# demo_74HC595_Shift_register.net
KiCad netlist of a schematic drawn in EasyEDA
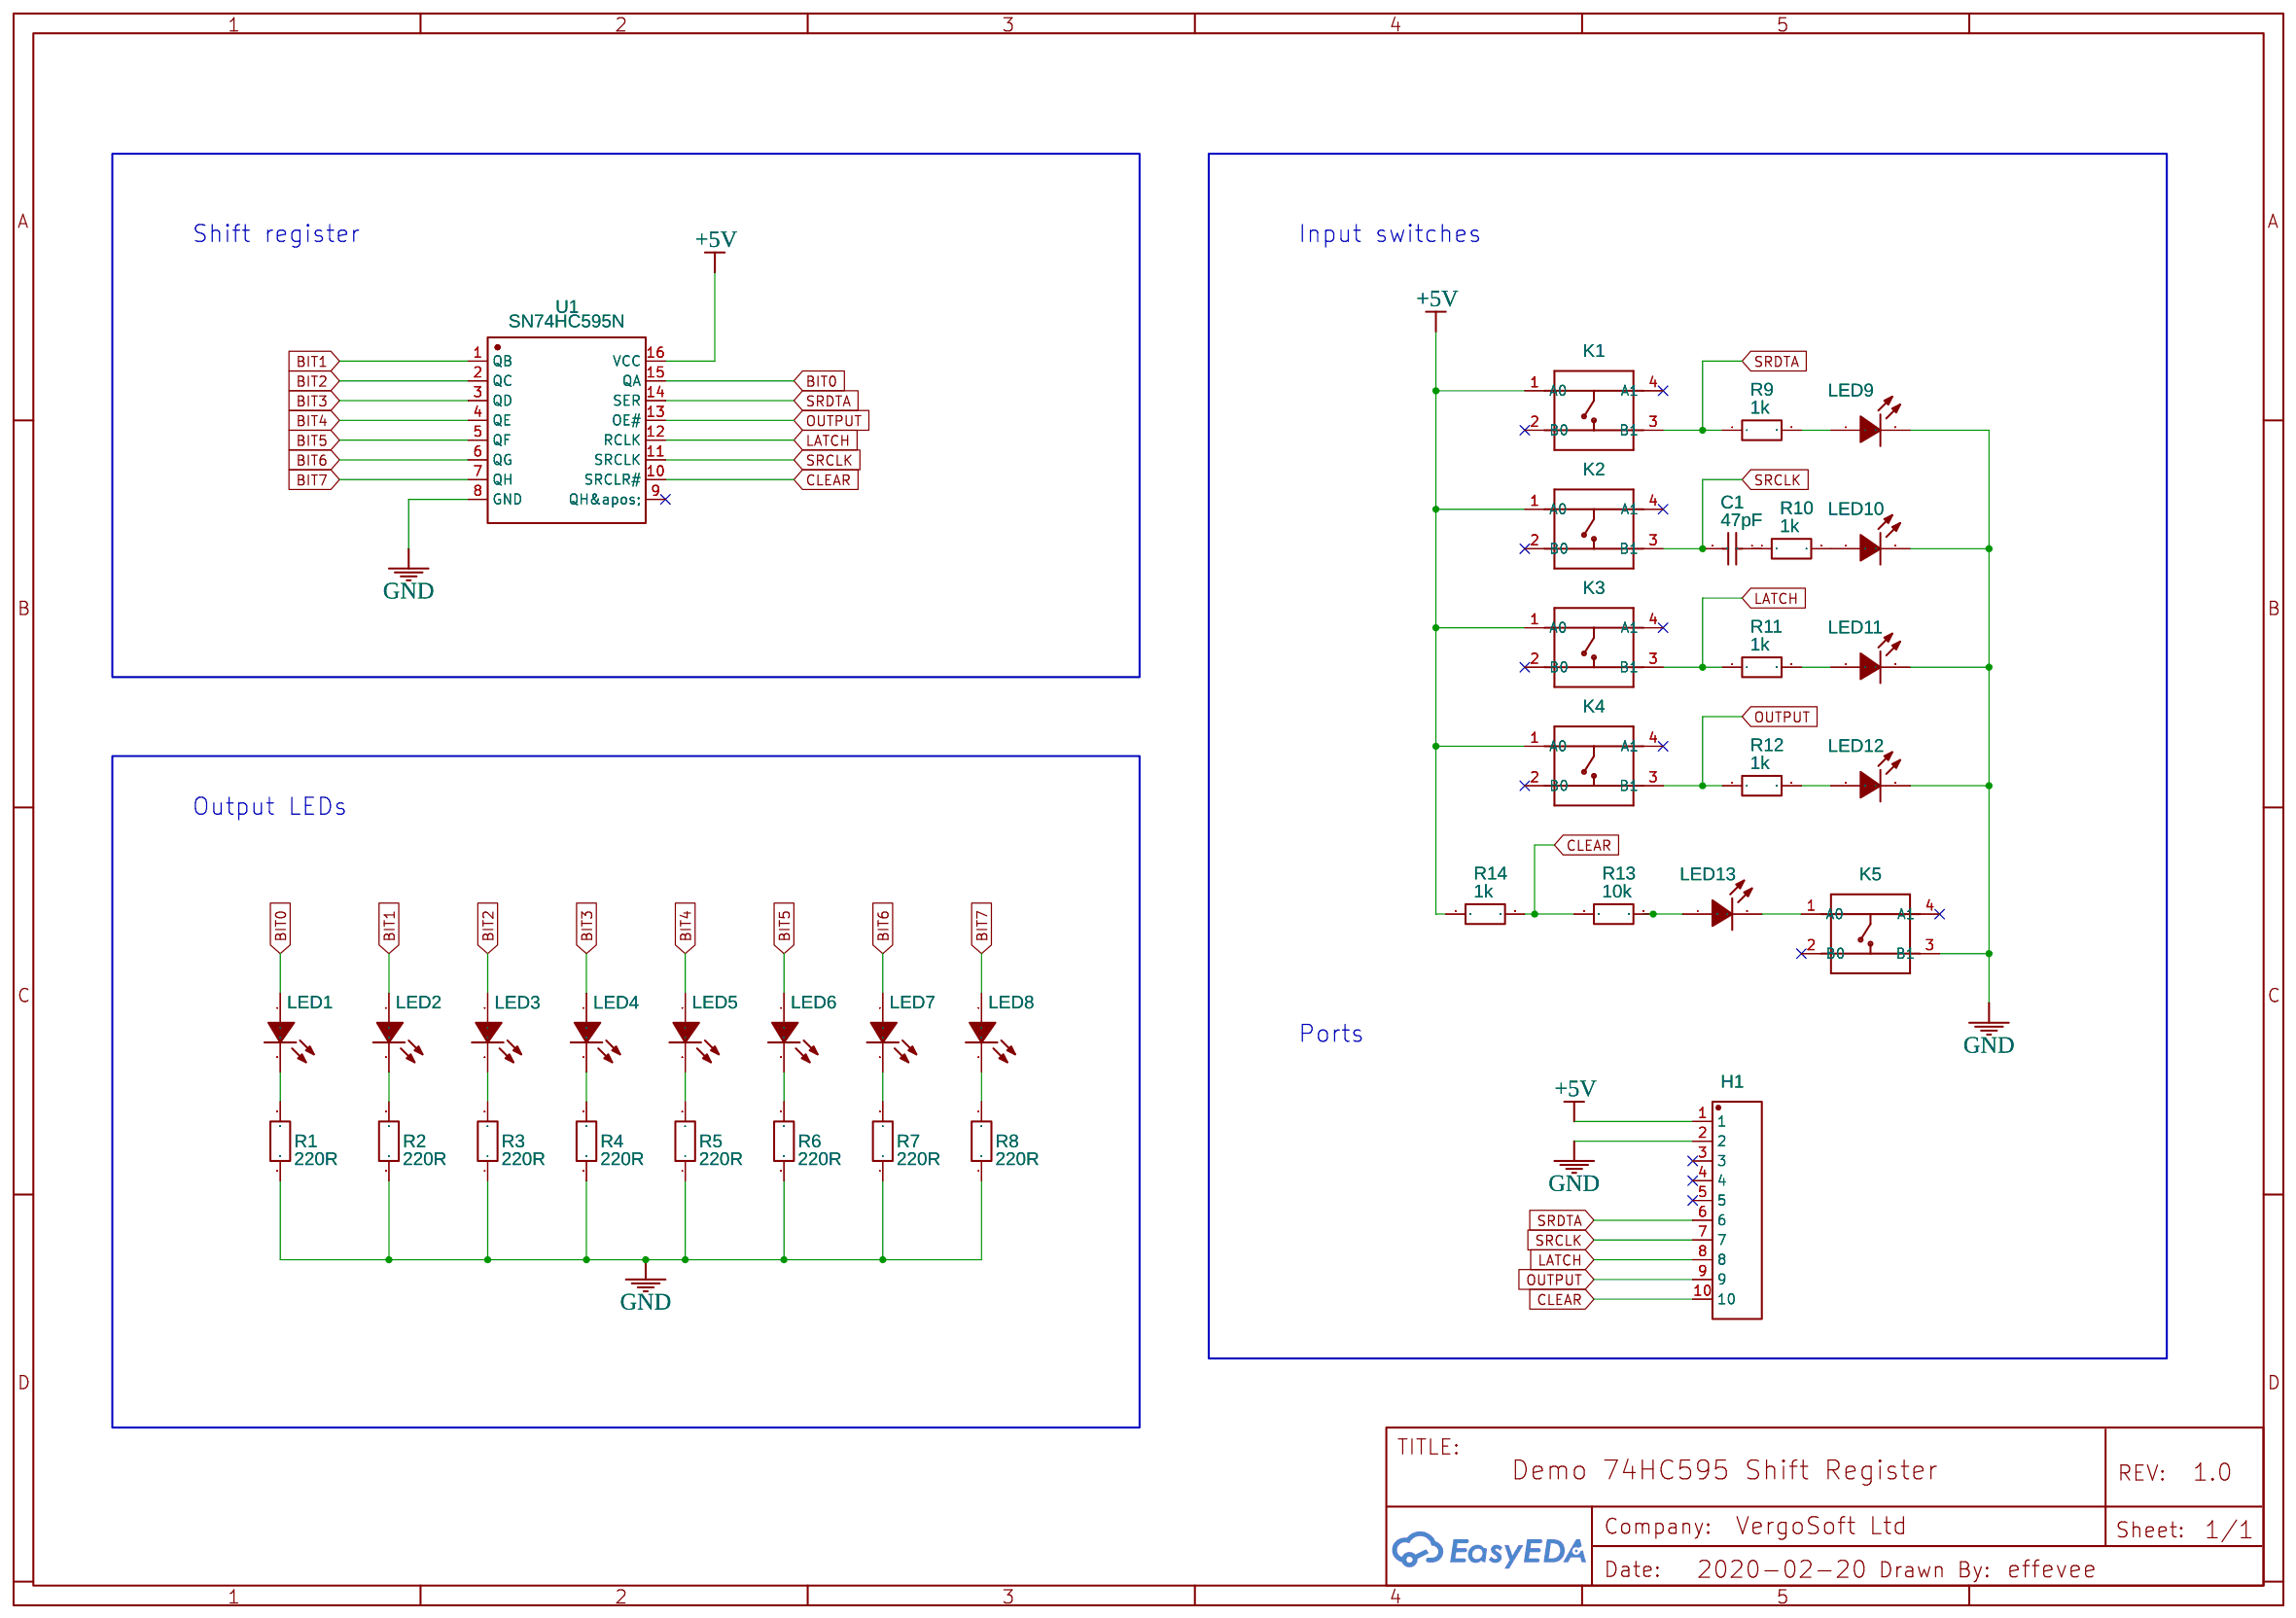
[diagram p0: schematic sheet]

(export (version "E")
  (design (tool "Eeschema 10.0.6"))
  (components
    (comp (ref "C1")
      (value "47pF")
      (fields
        (field (name "BOM_Manufacturer Part") "22pf/50V 10%")
        (field (name "BOM_Supplier Part") "C9316")
      )
      (libsource (lib "") (part "22pF"))
    )
    (comp (ref "H1")
      (value "Header-Male-2.54_1x10")
      (fields
        (field (name "BOM_Manufacturer Part") "Headers  Pins2.54mm1*10P")
        (field (name "BOM_Supplier Part") "C57369")
      )
      (libsource (lib "") (part "Header-Male-2.54_1x10"))
    )
    (comp (ref "K1")
      (value "DIP-SWITCH-TACTILE-SPST-NO_TS-1109(4P-D6.0MM)TS-1109")
      (libsource (lib "") (part "DIP-SWITCH-TACTILE-SPST-NO_TS-1109(4P-D6.0MM)TS-1109"))
    )
    (comp (ref "K2")
      (value "DIP-SWITCH-TACTILE-SPST-NO_TS-1109(4P-D6.0MM)TS-1109")
      (libsource (lib "") (part "DIP-SWITCH-TACTILE-SPST-NO_TS-1109(4P-D6.0MM)TS-1109"))
    )
    (comp (ref "K3")
      (value "DIP-SWITCH-TACTILE-SPST-NO_TS-1109(4P-D6.0MM)TS-1109")
      (libsource (lib "") (part "DIP-SWITCH-TACTILE-SPST-NO_TS-1109(4P-D6.0MM)TS-1109"))
    )
    (comp (ref "K4")
      (value "DIP-SWITCH-TACTILE-SPST-NO_TS-1109(4P-D6.0MM)TS-1109")
      (libsource (lib "") (part "DIP-SWITCH-TACTILE-SPST-NO_TS-1109(4P-D6.0MM)TS-1109"))
    )
    (comp (ref "K5")
      (value "DIP-SWITCH-TACTILE-SPST-NO_TS-1109(4P-D6.0MM)TS-1109")
      (libsource (lib "") (part "DIP-SWITCH-TACTILE-SPST-NO_TS-1109(4P-D6.0MM)TS-1109"))
    )
    (comp (ref "LED1")
      (value "204-10SURD/S530-A3")
      (fields (field (name "BOM_Supplier Part") "C99772"))
      (libsource (lib "") (part "204-10SURD/S530-A3"))
    )
    (comp (ref "LED2")
      (value "204-10SURD/S530-A3")
      (fields (field (name "BOM_Supplier Part") "C99772"))
      (libsource (lib "") (part "204-10SURD/S530-A3"))
    )
    (comp (ref "LED3")
      (value "204-10SURD/S530-A3")
      (fields (field (name "BOM_Supplier Part") "C99772"))
      (libsource (lib "") (part "204-10SURD/S530-A3"))
    )
    (comp (ref "LED4")
      (value "204-10SURD/S530-A3")
      (fields (field (name "BOM_Supplier Part") "C99772"))
      (libsource (lib "") (part "204-10SURD/S530-A3"))
    )
    (comp (ref "LED5")
      (value "204-10SURD/S530-A3")
      (fields (field (name "BOM_Supplier Part") "C99772"))
      (libsource (lib "") (part "204-10SURD/S530-A3"))
    )
    (comp (ref "LED6")
      (value "204-10SURD/S530-A3")
      (fields (field (name "BOM_Supplier Part") "C99772"))
      (libsource (lib "") (part "204-10SURD/S530-A3"))
    )
    (comp (ref "LED7")
      (value "204-10SURD/S530-A3")
      (fields (field (name "BOM_Supplier Part") "C99772"))
      (libsource (lib "") (part "204-10SURD/S530-A3"))
    )
    (comp (ref "LED8")
      (value "204-10SURD/S530-A3")
      (fields (field (name "BOM_Supplier Part") "C99772"))
      (libsource (lib "") (part "204-10SURD/S530-A3"))
    )
    (comp (ref "LED9")
      (value "204-10SURD/S530-A3")
      (fields (field (name "BOM_Supplier Part") "C99772"))
      (libsource (lib "") (part "204-10SURD/S530-A3_1"))
    )
    (comp (ref "LED10")
      (value "204-10SURD/S530-A3")
      (fields (field (name "BOM_Supplier Part") "C99772"))
      (libsource (lib "") (part "204-10SURD/S530-A3_1"))
    )
    (comp (ref "LED11")
      (value "204-10SURD/S530-A3")
      (fields (field (name "BOM_Supplier Part") "C99772"))
      (libsource (lib "") (part "204-10SURD/S530-A3_1"))
    )
    (comp (ref "LED12")
      (value "204-10SURD/S530-A3")
      (fields (field (name "BOM_Supplier Part") "C99772"))
      (libsource (lib "") (part "204-10SURD/S530-A3_1"))
    )
    (comp (ref "LED13")
      (value "204-10SURD/S530-A3")
      (fields (field (name "BOM_Supplier Part") "C99772"))
      (libsource (lib "") (part "204-10SURD/S530-A3_1"))
    )
    (comp (ref "R1") (value "220R") (libsource (lib "") (part "Res_AXIAL-0.3(1/8W)_EU")))
    (comp (ref "R2") (value "220R") (libsource (lib "") (part "Res_AXIAL-0.3(1/8W)_EU")))
    (comp (ref "R3") (value "220R") (libsource (lib "") (part "Res_AXIAL-0.3(1/8W)_EU")))
    (comp (ref "R4") (value "220R") (libsource (lib "") (part "Res_AXIAL-0.3(1/8W)_EU")))
    (comp (ref "R5") (value "220R") (libsource (lib "") (part "Res_AXIAL-0.3(1/8W)_EU")))
    (comp (ref "R6") (value "220R") (libsource (lib "") (part "Res_AXIAL-0.3(1/8W)_EU")))
    (comp (ref "R7") (value "220R") (libsource (lib "") (part "Res_AXIAL-0.3(1/8W)_EU")))
    (comp (ref "R8") (value "220R") (libsource (lib "") (part "Res_AXIAL-0.3(1/8W)_EU")))
    (comp (ref "R9") (value "1k") (libsource (lib "") (part "Res_AXIAL-0.3(1/8W)_EU_1")))
    (comp (ref "R10") (value "1k") (libsource (lib "") (part "Res_AXIAL-0.3(1/8W)_EU_1")))
    (comp (ref "R11") (value "1k") (libsource (lib "") (part "Res_AXIAL-0.3(1/8W)_EU_1")))
    (comp (ref "R12") (value "1k") (libsource (lib "") (part "Res_AXIAL-0.3(1/8W)_EU_1")))
    (comp (ref "R13") (value "10k") (libsource (lib "") (part "Res_AXIAL-0.3(1/8W)_EU_1")))
    (comp (ref "R14") (value "1k") (libsource (lib "") (part "Res_AXIAL-0.3(1/8W)_EU_1")))
    (comp (ref "U1")
      (value "SN74HC595N")
      (fields (field (name "BOM_Supplier Part") "C78711"))
      (libsource (lib "") (part "SN74HC595N"))
    )
  )
  (nets
    (net (code "1") (name "+5V") (class "Default")
      (node (ref "H1") (pin "1") (pinfunction "1_1") (pintype "unspecified"))
      (node (ref "K1") (pin "1") (pinfunction "A0_1") (pintype "unspecified"))
      (node (ref "K2") (pin "1") (pinfunction "A0_1") (pintype "unspecified"))
      (node (ref "K3") (pin "1") (pinfunction "A0_1") (pintype "unspecified"))
      (node (ref "K4") (pin "1") (pinfunction "A0_1") (pintype "unspecified"))
      (node (ref "R14") (pin "1") (pinfunction "1_1") (pintype "unspecified"))
      (node (ref "U1") (pin "16") (pinfunction "VCC_16") (pintype "unspecified"))
    )
    (net (code "2") (name "BIT0") (class "Default")
      (node (ref "LED1") (pin "1") (pinfunction "A_1") (pintype "unspecified"))
      (node (ref "U1") (pin "15") (pinfunction "QA_15") (pintype "unspecified"))
    )
    (net (code "3") (name "BIT1") (class "Default")
      (node (ref "LED2") (pin "1") (pinfunction "A_1") (pintype "unspecified"))
      (node (ref "U1") (pin "1") (pinfunction "QB_1") (pintype "unspecified"))
    )
    (net (code "4") (name "BIT2") (class "Default")
      (node (ref "LED3") (pin "1") (pinfunction "A_1") (pintype "unspecified"))
      (node (ref "U1") (pin "2") (pinfunction "QC_2") (pintype "unspecified"))
    )
    (net (code "5") (name "BIT3") (class "Default")
      (node (ref "LED4") (pin "1") (pinfunction "A_1") (pintype "unspecified"))
      (node (ref "U1") (pin "3") (pinfunction "QD_3") (pintype "unspecified"))
    )
    (net (code "6") (name "BIT4") (class "Default")
      (node (ref "LED5") (pin "1") (pinfunction "A_1") (pintype "unspecified"))
      (node (ref "U1") (pin "4") (pinfunction "QE_4") (pintype "unspecified"))
    )
    (net (code "7") (name "BIT5") (class "Default")
      (node (ref "LED6") (pin "1") (pinfunction "A_1") (pintype "unspecified"))
      (node (ref "U1") (pin "5") (pinfunction "QF_5") (pintype "unspecified"))
    )
    (net (code "8") (name "BIT6") (class "Default")
      (node (ref "LED7") (pin "1") (pinfunction "A_1") (pintype "unspecified"))
      (node (ref "U1") (pin "6") (pinfunction "QG_6") (pintype "unspecified"))
    )
    (net (code "9") (name "BIT7") (class "Default")
      (node (ref "LED8") (pin "1") (pinfunction "A_1") (pintype "unspecified"))
      (node (ref "U1") (pin "7") (pinfunction "QH_7") (pintype "unspecified"))
    )
    (net (code "10") (name "CLEAR") (class "Default")
      (node (ref "H1") (pin "10") (pinfunction "10_10") (pintype "unspecified"))
      (node (ref "R13") (pin "1") (pinfunction "1_1") (pintype "unspecified"))
      (node (ref "R14") (pin "2") (pinfunction "2_2") (pintype "unspecified"))
      (node (ref "U1") (pin "10") (pinfunction "SRCLR#_10") (pintype "unspecified"))
    )
    (net (code "11") (name "GND") (class "Default")
      (node (ref "H1") (pin "2") (pinfunction "2_2") (pintype "unspecified"))
      (node (ref "K5") (pin "3") (pinfunction "B1_3") (pintype "unspecified"))
      (node (ref "LED10") (pin "2") (pinfunction "K_2") (pintype "unspecified"))
      (node (ref "LED11") (pin "2") (pinfunction "K_2") (pintype "unspecified"))
      (node (ref "LED12") (pin "2") (pinfunction "K_2") (pintype "unspecified"))
      (node (ref "LED9") (pin "2") (pinfunction "K_2") (pintype "unspecified"))
      (node (ref "R1") (pin "1") (pinfunction "1_1") (pintype "unspecified"))
      (node (ref "R2") (pin "1") (pinfunction "1_1") (pintype "unspecified"))
      (node (ref "R3") (pin "1") (pinfunction "1_1") (pintype "unspecified"))
      (node (ref "R4") (pin "1") (pinfunction "1_1") (pintype "unspecified"))
      (node (ref "R5") (pin "1") (pinfunction "1_1") (pintype "unspecified"))
      (node (ref "R6") (pin "1") (pinfunction "1_1") (pintype "unspecified"))
      (node (ref "R7") (pin "1") (pinfunction "1_1") (pintype "unspecified"))
      (node (ref "R8") (pin "1") (pinfunction "1_1") (pintype "unspecified"))
      (node (ref "U1") (pin "8") (pinfunction "GND_8") (pintype "unspecified"))
    )
    (net (code "12") (name "LATCH") (class "Default")
      (node (ref "H1") (pin "8") (pinfunction "8_8") (pintype "unspecified"))
      (node (ref "K3") (pin "3") (pinfunction "B1_3") (pintype "unspecified"))
      (node (ref "R11") (pin "1") (pinfunction "1_1") (pintype "unspecified"))
      (node (ref "U1") (pin "12") (pinfunction "RCLK_12") (pintype "unspecified"))
    )
    (net (code "13") (name "Net-(C1-Pad2)") (class "Default")
      (node (ref "C1") (pin "2") (pinfunction "2_2") (pintype "input"))
      (node (ref "R10") (pin "1") (pinfunction "1_1") (pintype "unspecified"))
    )
    (net (code "14") (name "Net-(K5-A0)") (class "Default")
      (node (ref "K5") (pin "1") (pinfunction "A0_1") (pintype "unspecified"))
      (node (ref "LED13") (pin "2") (pinfunction "K_2") (pintype "unspecified"))
    )
    (net (code "15") (name "Net-(LED1-K)") (class "Default")
      (node (ref "LED1") (pin "2") (pinfunction "K_2") (pintype "unspecified"))
      (node (ref "R1") (pin "2") (pinfunction "2_2") (pintype "unspecified"))
    )
    (net (code "16") (name "Net-(LED2-K)") (class "Default")
      (node (ref "LED2") (pin "2") (pinfunction "K_2") (pintype "unspecified"))
      (node (ref "R2") (pin "2") (pinfunction "2_2") (pintype "unspecified"))
    )
    (net (code "17") (name "Net-(LED3-K)") (class "Default")
      (node (ref "LED3") (pin "2") (pinfunction "K_2") (pintype "unspecified"))
      (node (ref "R3") (pin "2") (pinfunction "2_2") (pintype "unspecified"))
    )
    (net (code "18") (name "Net-(LED4-K)") (class "Default")
      (node (ref "LED4") (pin "2") (pinfunction "K_2") (pintype "unspecified"))
      (node (ref "R4") (pin "2") (pinfunction "2_2") (pintype "unspecified"))
    )
    (net (code "19") (name "Net-(LED5-K)") (class "Default")
      (node (ref "LED5") (pin "2") (pinfunction "K_2") (pintype "unspecified"))
      (node (ref "R5") (pin "2") (pinfunction "2_2") (pintype "unspecified"))
    )
    (net (code "20") (name "Net-(LED6-K)") (class "Default")
      (node (ref "LED6") (pin "2") (pinfunction "K_2") (pintype "unspecified"))
      (node (ref "R6") (pin "2") (pinfunction "2_2") (pintype "unspecified"))
    )
    (net (code "21") (name "Net-(LED7-K)") (class "Default")
      (node (ref "LED7") (pin "2") (pinfunction "K_2") (pintype "unspecified"))
      (node (ref "R7") (pin "2") (pinfunction "2_2") (pintype "unspecified"))
    )
    (net (code "22") (name "Net-(LED8-K)") (class "Default")
      (node (ref "LED8") (pin "2") (pinfunction "K_2") (pintype "unspecified"))
      (node (ref "R8") (pin "2") (pinfunction "2_2") (pintype "unspecified"))
    )
    (net (code "23") (name "Net-(LED9-A)") (class "Default")
      (node (ref "LED9") (pin "1") (pinfunction "A_1") (pintype "unspecified"))
      (node (ref "R9") (pin "2") (pinfunction "2_2") (pintype "unspecified"))
    )
    (net (code "24") (name "Net-(LED10-A)") (class "Default")
      (node (ref "LED10") (pin "1") (pinfunction "A_1") (pintype "unspecified"))
      (node (ref "R10") (pin "2") (pinfunction "2_2") (pintype "unspecified"))
    )
    (net (code "25") (name "Net-(LED11-A)") (class "Default")
      (node (ref "LED11") (pin "1") (pinfunction "A_1") (pintype "unspecified"))
      (node (ref "R11") (pin "2") (pinfunction "2_2") (pintype "unspecified"))
    )
    (net (code "26") (name "Net-(LED12-A)") (class "Default")
      (node (ref "LED12") (pin "1") (pinfunction "A_1") (pintype "unspecified"))
      (node (ref "R12") (pin "2") (pinfunction "2_2") (pintype "unspecified"))
    )
    (net (code "27") (name "Net-(LED13-A)") (class "Default")
      (node (ref "LED13") (pin "1") (pinfunction "A_1") (pintype "unspecified"))
      (node (ref "R13") (pin "2") (pinfunction "2_2") (pintype "unspecified"))
    )
    (net (code "28") (name "OUTPUT") (class "Default")
      (node (ref "H1") (pin "9") (pinfunction "9_9") (pintype "unspecified"))
      (node (ref "K4") (pin "3") (pinfunction "B1_3") (pintype "unspecified"))
      (node (ref "R12") (pin "1") (pinfunction "1_1") (pintype "unspecified"))
      (node (ref "U1") (pin "13") (pinfunction "OE#_13") (pintype "unspecified"))
    )
    (net (code "29") (name "SRCLK") (class "Default")
      (node (ref "C1") (pin "1") (pinfunction "1_1") (pintype "input"))
      (node (ref "H1") (pin "7") (pinfunction "7_7") (pintype "unspecified"))
      (node (ref "K2") (pin "3") (pinfunction "B1_3") (pintype "unspecified"))
      (node (ref "U1") (pin "11") (pinfunction "SRCLK_11") (pintype "unspecified"))
    )
    (net (code "30") (name "SRDTA") (class "Default")
      (node (ref "H1") (pin "6") (pinfunction "6_6") (pintype "unspecified"))
      (node (ref "K1") (pin "3") (pinfunction "B1_3") (pintype "unspecified"))
      (node (ref "R9") (pin "1") (pinfunction "1_1") (pintype "unspecified"))
      (node (ref "U1") (pin "14") (pinfunction "SER_14") (pintype "unspecified"))
    )
    (net (code "31") (name "unconnected-(H1-Pad3)") (class "Default")
      (node (ref "H1") (pin "3") (pinfunction "3_3") (pintype "unspecified+no_connect"))
    )
    (net (code "32") (name "unconnected-(H1-Pad4)") (class "Default")
      (node (ref "H1") (pin "4") (pinfunction "4_4") (pintype "unspecified+no_connect"))
    )
    (net (code "33") (name "unconnected-(H1-Pad5)") (class "Default")
      (node (ref "H1") (pin "5") (pinfunction "5_5") (pintype "unspecified+no_connect"))
    )
    (net (code "34") (name "unconnected-(K1-A1-Pad4)") (class "Default")
      (node (ref "K1") (pin "4") (pinfunction "A1_4") (pintype "unspecified+no_connect"))
    )
    (net (code "35") (name "unconnected-(K1-B0-Pad2)") (class "Default")
      (node (ref "K1") (pin "2") (pinfunction "B0_2") (pintype "unspecified+no_connect"))
    )
    (net (code "36") (name "unconnected-(K2-A1-Pad4)") (class "Default")
      (node (ref "K2") (pin "4") (pinfunction "A1_4") (pintype "unspecified+no_connect"))
    )
    (net (code "37") (name "unconnected-(K2-B0-Pad2)") (class "Default")
      (node (ref "K2") (pin "2") (pinfunction "B0_2") (pintype "unspecified+no_connect"))
    )
    (net (code "38") (name "unconnected-(K3-A1-Pad4)") (class "Default")
      (node (ref "K3") (pin "4") (pinfunction "A1_4") (pintype "unspecified+no_connect"))
    )
    (net (code "39") (name "unconnected-(K3-B0-Pad2)") (class "Default")
      (node (ref "K3") (pin "2") (pinfunction "B0_2") (pintype "unspecified+no_connect"))
    )
    (net (code "40") (name "unconnected-(K4-A1-Pad4)") (class "Default")
      (node (ref "K4") (pin "4") (pinfunction "A1_4") (pintype "unspecified+no_connect"))
    )
    (net (code "41") (name "unconnected-(K4-B0-Pad2)") (class "Default")
      (node (ref "K4") (pin "2") (pinfunction "B0_2") (pintype "unspecified+no_connect"))
    )
    (net (code "42") (name "unconnected-(K5-A1-Pad4)") (class "Default")
      (node (ref "K5") (pin "4") (pinfunction "A1_4") (pintype "unspecified+no_connect"))
    )
    (net (code "43") (name "unconnected-(K5-B0-Pad2)") (class "Default")
      (node (ref "K5") (pin "2") (pinfunction "B0_2") (pintype "unspecified+no_connect"))
    )
    (net (code "44") (name "unconnected-(U1-QH&apos;-Pad9)") (class "Default")
      (node (ref "U1") (pin "9") (pinfunction "QH&apos;_9") (pintype "unspecified+no_connect"))
    )
  )
)
